# IoT_modules_atmega328_kinemata_v3.net
KiCad netlist of a schematic drawn in EAGLE
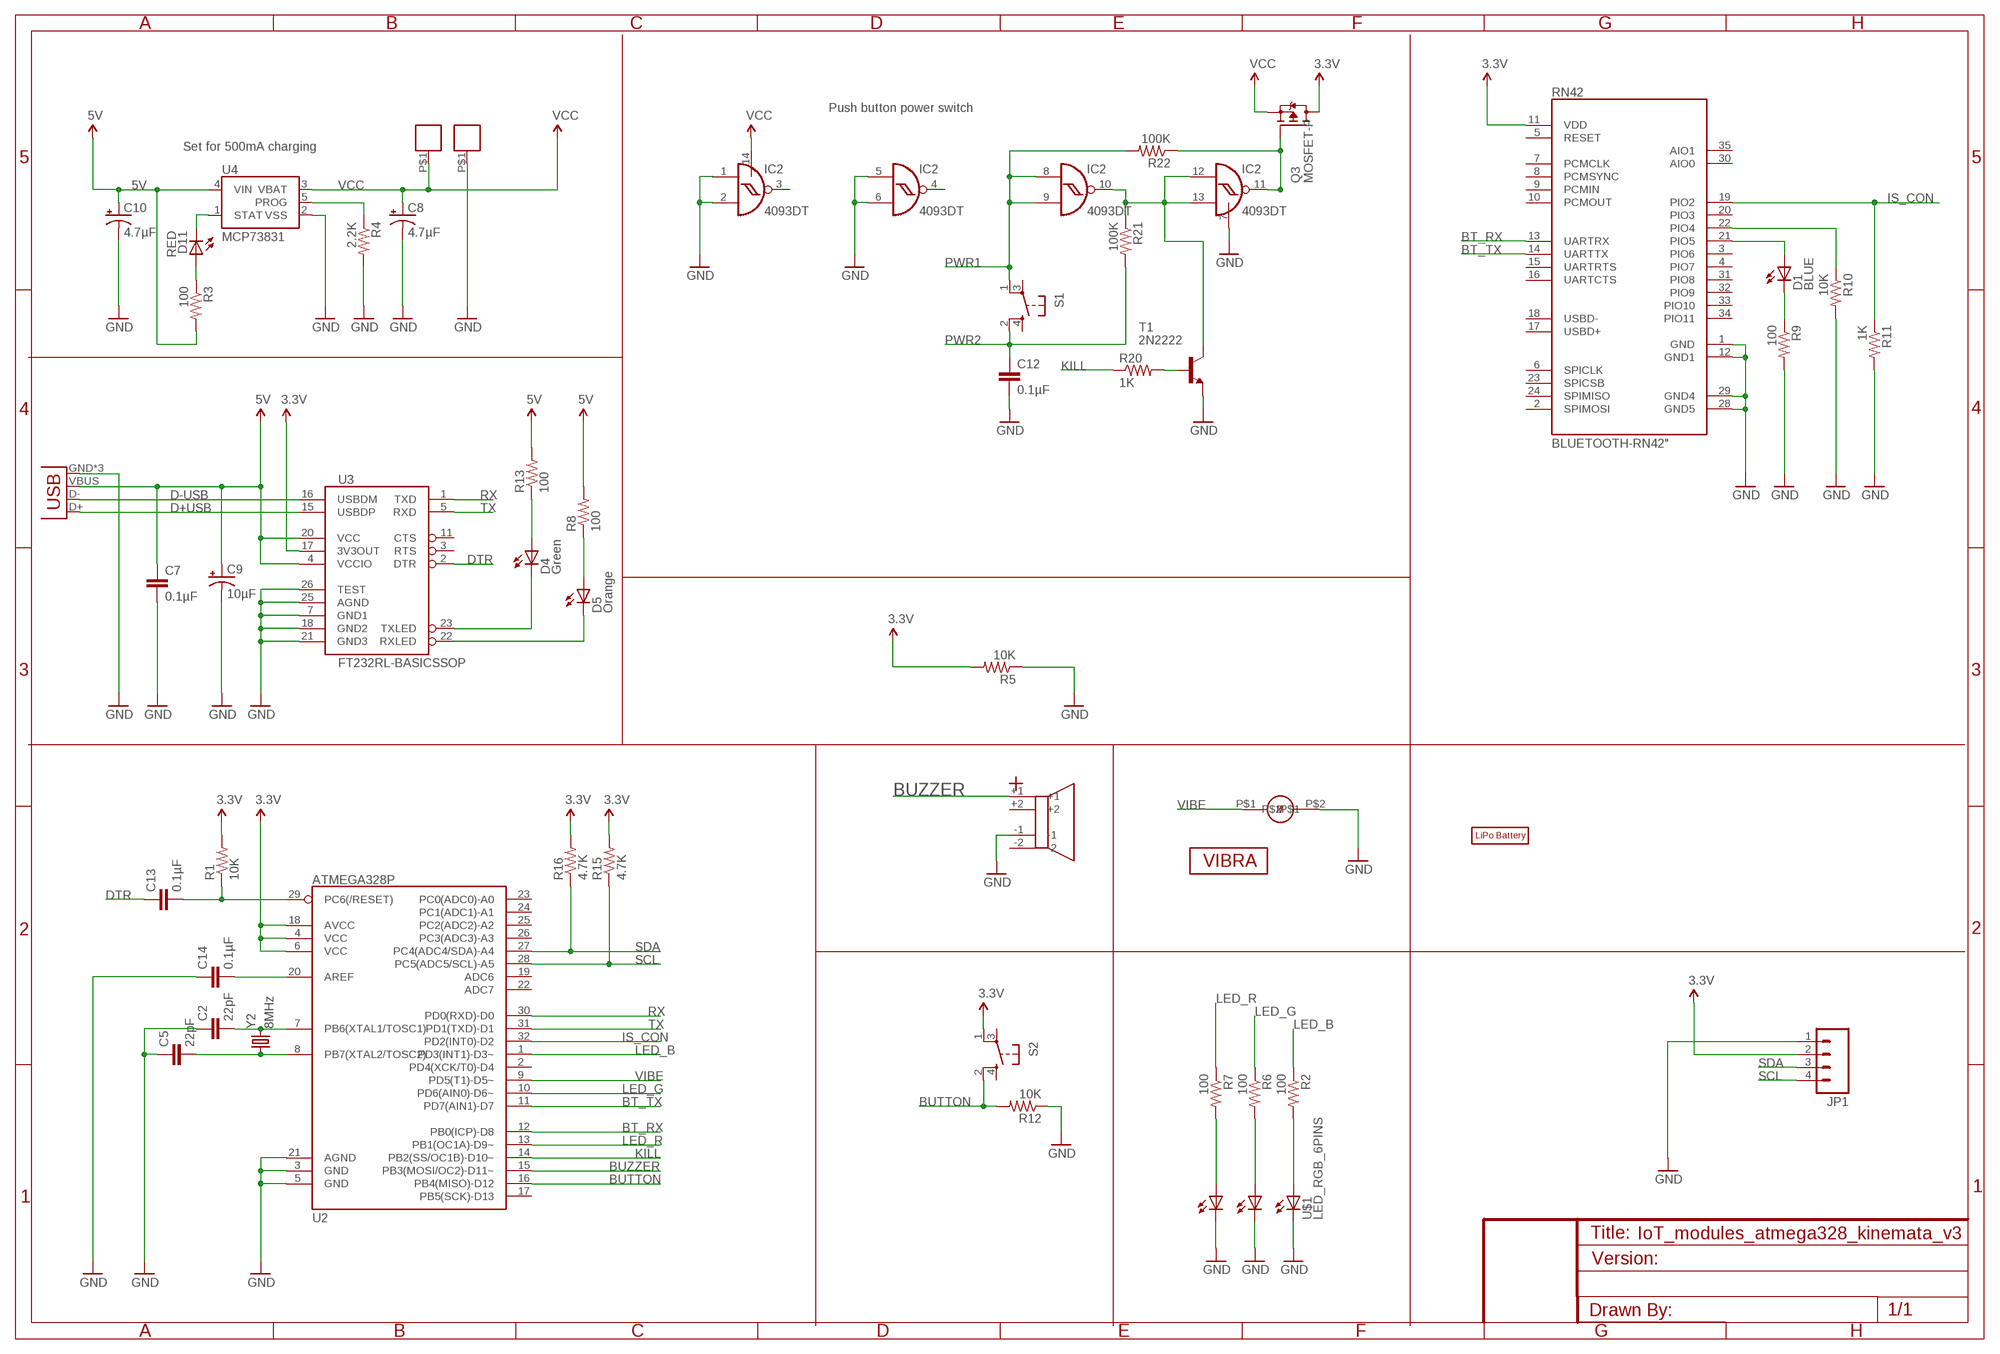
[diagram p0: schematic, sheet 1]

(export (version "E")
  (design (tool "Eeschema 10.0.6"))
  (components
    (comp (ref "BAT+2")
      (value "LIPO_PAD")
      (footprint "eagle-import:LIPO_PAD")
      (libsource (lib "eagle-import") (part "LIPO_PAD"))
    )
    (comp (ref "BAT-1")
      (value "LIPO_PAD")
      (footprint "eagle-import:LIPO_PAD")
      (libsource (lib "eagle-import") (part "LIPO_PAD"))
    )
    (comp (ref "C2")
      (value "22pF")
      (footprint "eagle-import:1206")
      (libsource (lib "eagle-import") (part "CAP1206"))
    )
    (comp (ref "C5")
      (value "22pF")
      (footprint "eagle-import:1206")
      (libsource (lib "eagle-import") (part "CAP1206"))
    )
    (comp (ref "C7")
      (value "0.1µF")
      (footprint "eagle-import:1206")
      (libsource (lib "eagle-import") (part "CAP1206"))
    )
    (comp (ref "C8")
      (value "4.7µF")
      (footprint "eagle-import:EIA3216")
      (libsource (lib "eagle-import") (part "CAP_POL1206"))
    )
    (comp (ref "C9")
      (value "10µF")
      (footprint "eagle-import:EIA3216")
      (libsource (lib "eagle-import") (part "CAP_POL1206"))
    )
    (comp (ref "C10")
      (value "4.7µF")
      (footprint "eagle-import:EIA3216")
      (libsource (lib "eagle-import") (part "CAP_POL1206"))
    )
    (comp (ref "C12")
      (value "0.1µF")
      (footprint "eagle-import:1206")
      (libsource (lib "eagle-import") (part "CAP1206"))
    )
    (comp (ref "C13")
      (value "0.1µF")
      (footprint "eagle-import:1206")
      (libsource (lib "eagle-import") (part "CAP1206"))
    )
    (comp (ref "C14")
      (value "0.1µF")
      (footprint "eagle-import:1206")
      (libsource (lib "eagle-import") (part "CAP1206"))
    )
    (comp (ref "D1")
      (value "BLUE")
      (footprint "eagle-import:LED-1206")
      (libsource (lib "eagle-import") (part "LED1206"))
    )
    (comp (ref "D4")
      (value "Green")
      (footprint "eagle-import:LED-1206")
      (libsource (lib "eagle-import") (part "LED1206"))
    )
    (comp (ref "D5")
      (value "Orange")
      (footprint "eagle-import:LED-1206")
      (libsource (lib "eagle-import") (part "LED1206"))
    )
    (comp (ref "D11")
      (value "RED")
      (footprint "eagle-import:LED-1206")
      (libsource (lib "eagle-import") (part "LED1206"))
    )
    (comp (ref "IC2")
      (value "4093DT")
      (footprint "eagle-import:MC14093B-TSSOP14")
      (libsource (lib "eagle-import") (part "4093DT"))
    )
    (comp (ref "JP1")
      (value "M04LONGPADS")
      (footprint "eagle-import:1X04_LONGPADS")
      (libsource (lib "eagle-import") (part "M04LONGPADS"))
    )
    (comp (ref "JP6")
      (value "USB-MICROB")
      (footprint "eagle-import:USB-MICROB")
      (libsource (lib "eagle-import") (part "USB-MICROB"))
    )
    (comp (ref "Q3")
      (value "MOSFET-P")
      (footprint "eagle-import:SOT23")
      (libsource (lib "eagle-import") (part "MOSFET-P"))
    )
    (comp (ref "R1")
      (value "10K")
      (footprint "eagle-import:1206")
      (libsource (lib "eagle-import") (part "RESISTOR1206"))
    )
    (comp (ref "R2")
      (value "100")
      (footprint "eagle-import:1206")
      (libsource (lib "eagle-import") (part "RESISTOR1206"))
    )
    (comp (ref "R3")
      (value "100")
      (footprint "eagle-import:1206")
      (libsource (lib "eagle-import") (part "RESISTOR1206"))
    )
    (comp (ref "R4")
      (value "2.2K")
      (footprint "eagle-import:1206")
      (libsource (lib "eagle-import") (part "RESISTOR1206"))
    )
    (comp (ref "R5")
      (value "10K")
      (footprint "eagle-import:1206")
      (libsource (lib "eagle-import") (part "RESISTOR1206"))
    )
    (comp (ref "R6")
      (value "100")
      (footprint "eagle-import:1206")
      (libsource (lib "eagle-import") (part "RESISTOR1206"))
    )
    (comp (ref "R7")
      (value "100")
      (footprint "eagle-import:1206")
      (libsource (lib "eagle-import") (part "RESISTOR1206"))
    )
    (comp (ref "R8")
      (value "100")
      (footprint "eagle-import:1206")
      (libsource (lib "eagle-import") (part "RESISTOR1206"))
    )
    (comp (ref "R9")
      (value "100")
      (footprint "eagle-import:1206")
      (libsource (lib "eagle-import") (part "RESISTOR1206"))
    )
    (comp (ref "R10")
      (value "10K")
      (footprint "eagle-import:1206")
      (libsource (lib "eagle-import") (part "RESISTOR1206"))
    )
    (comp (ref "R11")
      (value "1K")
      (footprint "eagle-import:1206")
      (libsource (lib "eagle-import") (part "RESISTOR1206"))
    )
    (comp (ref "R12")
      (value "10K")
      (footprint "eagle-import:1206")
      (libsource (lib "eagle-import") (part "RESISTOR1206"))
    )
    (comp (ref "R13")
      (value "100")
      (footprint "eagle-import:1206")
      (libsource (lib "eagle-import") (part "RESISTOR1206"))
    )
    (comp (ref "R15")
      (value "4.7K")
      (footprint "eagle-import:1206")
      (libsource (lib "eagle-import") (part "RESISTOR1206"))
    )
    (comp (ref "R16")
      (value "4.7K")
      (footprint "eagle-import:1206")
      (libsource (lib "eagle-import") (part "RESISTOR1206"))
    )
    (comp (ref "R20")
      (value "1K")
      (footprint "eagle-import:1206")
      (libsource (lib "eagle-import") (part "RESISTOR1206"))
    )
    (comp (ref "R21")
      (value "100K")
      (footprint "eagle-import:1206")
      (libsource (lib "eagle-import") (part "RESISTOR1206"))
    )
    (comp (ref "R22")
      (value "100K")
      (footprint "eagle-import:1206")
      (libsource (lib "eagle-import") (part "RESISTOR1206"))
    )
    (comp (ref "RN42")
      (value "BLUETOOTH-RN42\"")
      (footprint "eagle-import:RN42")
      (libsource (lib "eagle-import") (part "BLUETOOTH-RN42{dblquote}"))
    )
    (comp (ref "S1")
      (value "TAC_SWITCH_SIDEWAY")
      (footprint "eagle-import:TACTILE_SWITCH_ANGLE_SMD")
      (libsource (lib "eagle-import") (part "TAC_SWITCH_SIDEWAY"))
    )
    (comp (ref "S2")
      (value "TAC_SWITCH_SIDEWAY")
      (footprint "eagle-import:TACTILE_SWITCH_ANGLE_SMD")
      (libsource (lib "eagle-import") (part "TAC_SWITCH_SIDEWAY"))
    )
    (comp (ref "T1")
      (value "2N2222")
      (footprint "eagle-import:TO92-EBC-OVAL")
      (libsource (lib "eagle-import") (part "2N2222"))
    )
    (comp (ref "U$1")
      (value "LED_RGB_6PINS")
      (footprint "eagle-import:LED_RGB_6PINS")
      (libsource (lib "eagle-import") (part "LED_RGB_6PINS"))
    )
    (comp (ref "U$2")
      (value "LIPO_BATTERY110MAH")
      (footprint "eagle-import:LIPO_BATTERY_110MAH")
      (libsource (lib "eagle-import") (part "LIPO_BATTERY110MAH"))
    )
    (comp (ref "U$3")
      (value "BUZZER_4PINS")
      (footprint "eagle-import:FARNELL_BUZZER_MAGNETIC_SMD_3V_2215091")
      (libsource (lib "eagle-import") (part "BUZZER_4PINS"))
    )
    (comp (ref "U$4")
      (value "VIBRATION_MOTOR_SHAPE")
      (footprint "eagle-import:VIBRATION_MOTOR_SHAPE")
      (libsource (lib "eagle-import") (part "VIBRATION_MOTOR_SHAPE"))
    )
    (comp (ref "U$5")
      (value "VIBRATION_MOTOR")
      (footprint "eagle-import:VIBRATION_MOTOR_CABLE")
      (libsource (lib "eagle-import") (part "VIBRATION_MOTOR"))
    )
    (comp (ref "U2")
      (value "ATMEGA328P")
      (footprint "eagle-import:TQFP32-08")
      (libsource (lib "eagle-import") (part "ATMEGA328_SMT"))
    )
    (comp (ref "U3")
      (value "FT232RL-BASICSSOP")
      (footprint "eagle-import:SSOP28DB")
      (libsource (lib "eagle-import") (part "FT232RL-BASICSSOP"))
    )
    (comp (ref "U4")
      (value "MCP73831")
      (footprint "eagle-import:SOT23-5")
      (libsource (lib "eagle-import") (part "MCP73831"))
    )
    (comp (ref "Y2")
      (value "8MHz")
      (footprint "eagle-import:CRYSTAL_8MHZ_SMD_FARNELL_2101329")
      (libsource (lib "eagle-import") (part "CRYSTAL_2PINS5X3.2"))
    )
  )
  (nets
    (net (code "1") (name "/BT_RX") (class "Default")
      (node (ref "RN42") (pin "13") (pinfunction "UARTRX_13") (pintype "bidirectional"))
      (node (ref "U2") (pin "12") (pinfunction "PB0(ICP)-D8_12") (pintype "bidirectional"))
    )
    (net (code "2") (name "/BT_TX") (class "Default")
      (node (ref "RN42") (pin "14") (pinfunction "UARTTX_14") (pintype "bidirectional"))
      (node (ref "U2") (pin "11") (pinfunction "PD7(AIN1)-D7_11") (pintype "bidirectional"))
    )
    (net (code "3") (name "/BUTTON") (class "Default")
      (node (ref "R12") (pin "2") (pinfunction "2_2") (pintype "passive"))
      (node (ref "S2") (pin "2") (pinfunction "B2_2") (pintype "passive"))
      (node (ref "U2") (pin "16") (pinfunction "PB4(MISO)-D12_16") (pintype "bidirectional"))
    )
    (net (code "4") (name "/BUZZER") (class "Default")
      (node (ref "U$3") (pin "+1") (pinfunction "+1_+1") (pintype "bidirectional"))
      (node (ref "U2") (pin "15") (pinfunction "PB3(MOSI/OC2)-D11~{}_15") (pintype "bidirectional"))
    )
    (net (code "5") (name "/D+USB") (class "Default")
      (node (ref "JP6") (pin "D+") (pinfunction "D+_D+") (pintype "bidirectional"))
      (node (ref "U3") (pin "15") (pinfunction "USBDP_15") (pintype "bidirectional"))
    )
    (net (code "6") (name "/D-USB") (class "Default")
      (node (ref "JP6") (pin "D-") (pinfunction "D-_D-") (pintype "bidirectional"))
      (node (ref "U3") (pin "16") (pinfunction "USBDM_16") (pintype "bidirectional"))
    )
    (net (code "7") (name "/DTR") (class "Default")
      (node (ref "C13") (pin "1") (pinfunction "1_1") (pintype "passive"))
      (node (ref "U3") (pin "2") (pinfunction "DTR_2") (pintype "bidirectional"))
    )
    (net (code "8") (name "/IS_CON") (class "Default")
      (node (ref "R11") (pin "1") (pinfunction "1_1") (pintype "passive"))
      (node (ref "RN42") (pin "19") (pinfunction "PIO2_19") (pintype "bidirectional"))
      (node (ref "U2") (pin "32") (pinfunction "PD2(INT0)-D2_32") (pintype "bidirectional"))
    )
    (net (code "9") (name "/KILL") (class "Default")
      (node (ref "R20") (pin "1") (pinfunction "1_1") (pintype "passive"))
      (node (ref "U2") (pin "14") (pinfunction "PB2(SS/OC1B)-D10~{}_14") (pintype "bidirectional"))
    )
    (net (code "10") (name "/LED_B") (class "Default")
      (node (ref "R2") (pin "1") (pinfunction "1_1") (pintype "passive"))
      (node (ref "U2") (pin "1") (pinfunction "PD3(INT1)-D3~{}_1") (pintype "bidirectional"))
    )
    (net (code "11") (name "/LED_G") (class "Default")
      (node (ref "R6") (pin "1") (pinfunction "1_1") (pintype "passive"))
      (node (ref "U2") (pin "10") (pinfunction "PD6(AIN0)-D6~{}_10") (pintype "bidirectional"))
    )
    (net (code "12") (name "/LED_R") (class "Default")
      (node (ref "R7") (pin "1") (pinfunction "1_1") (pintype "passive"))
      (node (ref "U2") (pin "13") (pinfunction "PB1(OC1A)-D9~{}_13") (pintype "bidirectional"))
    )
    (net (code "13") (name "/PWR1") (class "Default")
      (node (ref "IC2") (pin "8") (pinfunction "8_8") (pintype "input"))
      (node (ref "IC2") (pin "9") (pinfunction "9_9") (pintype "input"))
      (node (ref "R22") (pin "2") (pinfunction "2_2") (pintype "passive"))
      (node (ref "S1") (pin "1") (pinfunction "A2_1") (pintype "passive"))
    )
    (net (code "14") (name "/PWR2") (class "Default")
      (node (ref "C12") (pin "1") (pinfunction "1_1") (pintype "passive"))
      (node (ref "R21") (pin "2") (pinfunction "2_2") (pintype "passive"))
      (node (ref "S1") (pin "2") (pinfunction "B2_2") (pintype "passive"))
    )
    (net (code "15") (name "/RX") (class "Default")
      (node (ref "U2") (pin "30") (pinfunction "PD0(RXD)-D0_30") (pintype "bidirectional"))
      (node (ref "U3") (pin "1") (pinfunction "TXD_1") (pintype "output"))
    )
    (net (code "16") (name "/SCL") (class "Default")
      (node (ref "JP1") (pin "4") (pinfunction "4_4") (pintype "passive"))
      (node (ref "R15") (pin "1") (pinfunction "1_1") (pintype "passive"))
      (node (ref "U2") (pin "28") (pinfunction "PC5(ADC5/SCL)-A5_28") (pintype "bidirectional"))
    )
    (net (code "17") (name "/SDA") (class "Default")
      (node (ref "JP1") (pin "3") (pinfunction "3_3") (pintype "passive"))
      (node (ref "R16") (pin "1") (pinfunction "1_1") (pintype "passive"))
      (node (ref "U2") (pin "27") (pinfunction "PC4(ADC4/SDA)-A4_27") (pintype "bidirectional"))
    )
    (net (code "18") (name "/TX") (class "Default")
      (node (ref "U2") (pin "31") (pinfunction "PD1(TXD)-D1_31") (pintype "bidirectional"))
      (node (ref "U3") (pin "5") (pinfunction "RXD_5") (pintype "input"))
    )
    (net (code "19") (name "/VIBE") (class "Default")
      (node (ref "U$5") (pin "P$1") (pinfunction "P$1_P$1") (pintype "bidirectional"))
      (node (ref "U2") (pin "9") (pinfunction "PD5(T1)-D5~{}_9") (pintype "bidirectional"))
    )
    (net (code "20") (name "3.3V") (class "Default")
      (node (ref "JP1") (pin "2") (pinfunction "2_2") (pintype "passive"))
      (node (ref "Q3") (pin "3") (pinfunction "D_3") (pintype "passive"))
      (node (ref "R1") (pin "2") (pinfunction "2_2") (pintype "passive"))
      (node (ref "R15") (pin "2") (pinfunction "2_2") (pintype "passive"))
      (node (ref "R16") (pin "2") (pinfunction "2_2") (pintype "passive"))
      (node (ref "R5") (pin "2") (pinfunction "2_2") (pintype "passive"))
      (node (ref "RN42") (pin "11") (pinfunction "VDD_11") (pintype "bidirectional"))
      (node (ref "S2") (pin "1") (pinfunction "A2_1") (pintype "passive"))
      (node (ref "U2") (pin "18") (pinfunction "AVCC_18") (pintype "bidirectional"))
      (node (ref "U2") (pin "4") (pinfunction "VCC_4") (pintype "bidirectional"))
      (node (ref "U2") (pin "6") (pinfunction "VCC_6") (pintype "bidirectional"))
      (node (ref "U3") (pin "17") (pinfunction "3V3OUT_17") (pintype "output"))
    )
    (net (code "21") (name "5V") (class "Default")
      (node (ref "C10") (pin "A") (pinfunction "+_A") (pintype "passive"))
      (node (ref "C7") (pin "1") (pinfunction "1_1") (pintype "passive"))
      (node (ref "C9") (pin "A") (pinfunction "+_A") (pintype "passive"))
      (node (ref "JP6") (pin "VBUS") (pinfunction "VBUS_VBUS") (pintype "bidirectional"))
      (node (ref "R13") (pin "2") (pinfunction "2_2") (pintype "passive"))
      (node (ref "R3") (pin "2") (pinfunction "2_2") (pintype "passive"))
      (node (ref "R8") (pin "2") (pinfunction "2_2") (pintype "passive"))
      (node (ref "U3") (pin "20") (pinfunction "VCC_20") (pintype "power_in"))
      (node (ref "U3") (pin "4") (pinfunction "VCCIO_4") (pintype "power_in"))
      (node (ref "U4") (pin "4") (pinfunction "VIN_4") (pintype "power_in"))
    )
    (net (code "22") (name "GND") (class "Default")
      (node (ref "BAT-1") (pin "P$1") (pinfunction "P$1_P$1") (pintype "power_in"))
      (node (ref "C10") (pin "C") (pinfunction "-_C") (pintype "passive"))
      (node (ref "C12") (pin "2") (pinfunction "2_2") (pintype "passive"))
      (node (ref "C14") (pin "1") (pinfunction "1_1") (pintype "passive"))
      (node (ref "C2") (pin "1") (pinfunction "1_1") (pintype "passive"))
      (node (ref "C5") (pin "1") (pinfunction "1_1") (pintype "passive"))
      (node (ref "C7") (pin "2") (pinfunction "2_2") (pintype "passive"))
      (node (ref "C8") (pin "C") (pinfunction "-_C") (pintype "passive"))
      (node (ref "C9") (pin "C") (pinfunction "-_C") (pintype "passive"))
      (node (ref "IC2") (pin "1") (pinfunction "1_1") (pintype "input"))
      (node (ref "IC2") (pin "2") (pinfunction "2_2") (pintype "input"))
      (node (ref "IC2") (pin "5") (pinfunction "5_5") (pintype "input"))
      (node (ref "IC2") (pin "6") (pinfunction "6_6") (pintype "input"))
      (node (ref "IC2") (pin "7") (pinfunction "7_7") (pintype "power_in"))
      (node (ref "JP1") (pin "1") (pinfunction "1_1") (pintype "passive"))
      (node (ref "JP6") (pin "GND") (pinfunction "GND_GND") (pintype "bidirectional"))
      (node (ref "JP6") (pin "MT1") (pinfunction "GND_MT1") (pintype "bidirectional"))
      (node (ref "JP6") (pin "MT2") (pinfunction "GND_MT2") (pintype "bidirectional"))
      (node (ref "R10") (pin "2") (pinfunction "2_2") (pintype "passive"))
      (node (ref "R11") (pin "2") (pinfunction "2_2") (pintype "passive"))
      (node (ref "R12") (pin "1") (pinfunction "1_1") (pintype "passive"))
      (node (ref "R4") (pin "2") (pinfunction "2_2") (pintype "passive"))
      (node (ref "R5") (pin "1") (pinfunction "1_1") (pintype "passive"))
      (node (ref "R9") (pin "2") (pinfunction "2_2") (pintype "passive"))
      (node (ref "RN42") (pin "1") (pinfunction "GND_1") (pintype "bidirectional"))
      (node (ref "RN42") (pin "12") (pinfunction "GND1_12") (pintype "bidirectional"))
      (node (ref "RN42") (pin "28") (pinfunction "GND5_28") (pintype "bidirectional"))
      (node (ref "RN42") (pin "29") (pinfunction "GND4_29") (pintype "bidirectional"))
      (node (ref "T1") (pin "E") (pinfunction "E_E") (pintype "passive"))
      (node (ref "U$1") (pin "BC") (pinfunction "BC_BC") (pintype "passive"))
      (node (ref "U$1") (pin "GC") (pinfunction "GC_GC") (pintype "passive"))
      (node (ref "U$1") (pin "RC") (pinfunction "RC_RC") (pintype "passive"))
      (node (ref "U$3") (pin "-1") (pinfunction "-1_-1") (pintype "bidirectional"))
      (node (ref "U$5") (pin "P$2") (pinfunction "P$2_P$2") (pintype "bidirectional"))
      (node (ref "U2") (pin "21") (pinfunction "AGND_21") (pintype "bidirectional"))
      (node (ref "U2") (pin "3") (pinfunction "GND_3") (pintype "bidirectional"))
      (node (ref "U2") (pin "5") (pinfunction "GND_5") (pintype "bidirectional"))
      (node (ref "U3") (pin "18") (pinfunction "GND2_18") (pintype "power_in"))
      (node (ref "U3") (pin "21") (pinfunction "GND3_21") (pintype "power_in"))
      (node (ref "U3") (pin "25") (pinfunction "AGND_25") (pintype "power_in"))
      (node (ref "U3") (pin "26") (pinfunction "TEST_26") (pintype "input"))
      (node (ref "U3") (pin "7") (pinfunction "GND1_7") (pintype "power_in"))
      (node (ref "U4") (pin "2") (pinfunction "VSS_2") (pintype "power_in"))
    )
    (net (code "23") (name "Net-(D1-PadC)") (class "Default")
      (node (ref "D1") (pin "C") (pinfunction "C_C") (pintype "passive"))
      (node (ref "R9") (pin "1") (pinfunction "1_1") (pintype "passive"))
    )
    (net (code "24") (name "Net-(D4-PadA)") (class "Default")
      (node (ref "D4") (pin "A") (pinfunction "A_A") (pintype "passive"))
      (node (ref "R13") (pin "1") (pinfunction "1_1") (pintype "passive"))
    )
    (net (code "25") (name "Net-(D5-PadA)") (class "Default")
      (node (ref "D5") (pin "A") (pinfunction "A_A") (pintype "passive"))
      (node (ref "R8") (pin "1") (pinfunction "1_1") (pintype "passive"))
    )
    (net (code "26") (name "Net-(D11-PadA)") (class "Default")
      (node (ref "D11") (pin "A") (pinfunction "A_A") (pintype "passive"))
      (node (ref "R3") (pin "1") (pinfunction "1_1") (pintype "passive"))
    )
    (net (code "27") (name "Net-(IC2-Pad10)") (class "Default")
      (node (ref "IC2") (pin "10") (pinfunction "10_10") (pintype "output"))
      (node (ref "IC2") (pin "12") (pinfunction "12_12") (pintype "input"))
      (node (ref "IC2") (pin "13") (pinfunction "13_13") (pintype "input"))
      (node (ref "R21") (pin "1") (pinfunction "1_1") (pintype "passive"))
      (node (ref "T1") (pin "C") (pinfunction "C_C") (pintype "passive"))
    )
    (net (code "28") (name "Net-(Q3-G)") (class "Default")
      (node (ref "IC2") (pin "11") (pinfunction "11_11") (pintype "output"))
      (node (ref "Q3") (pin "1") (pinfunction "G_1") (pintype "passive"))
      (node (ref "R22") (pin "1") (pinfunction "1_1") (pintype "passive"))
    )
    (net (code "29") (name "Net-(R2-Pad2)") (class "Default")
      (node (ref "R2") (pin "2") (pinfunction "2_2") (pintype "passive"))
      (node (ref "U$1") (pin "GA") (pinfunction "GA_GA") (pintype "passive"))
    )
    (net (code "30") (name "Net-(R6-Pad2)") (class "Default")
      (node (ref "R6") (pin "2") (pinfunction "2_2") (pintype "passive"))
      (node (ref "U$1") (pin "RA") (pinfunction "RA_RA") (pintype "passive"))
    )
    (net (code "31") (name "Net-(R7-Pad2)") (class "Default")
      (node (ref "R7") (pin "2") (pinfunction "2_2") (pintype "passive"))
      (node (ref "U$1") (pin "BA") (pinfunction "BA_BA") (pintype "passive"))
    )
    (net (code "32") (name "Net-(R20-Pad2)") (class "Default")
      (node (ref "R20") (pin "2") (pinfunction "2_2") (pintype "passive"))
      (node (ref "T1") (pin "B") (pinfunction "B_B") (pintype "passive"))
    )
    (net (code "33") (name "Net-(RN42-PIO4)") (class "Default")
      (node (ref "R10") (pin "1") (pinfunction "1_1") (pintype "passive"))
      (node (ref "RN42") (pin "22") (pinfunction "PIO4_22") (pintype "bidirectional"))
    )
    (net (code "34") (name "Net-(RN42-PIO5)") (class "Default")
      (node (ref "D1") (pin "A") (pinfunction "A_A") (pintype "passive"))
      (node (ref "RN42") (pin "21") (pinfunction "PIO5_21") (pintype "bidirectional"))
    )
    (net (code "35") (name "Net-(U2-AREF)") (class "Default")
      (node (ref "C14") (pin "2") (pinfunction "2_2") (pintype "passive"))
      (node (ref "U2") (pin "20") (pinfunction "AREF_20") (pintype "bidirectional"))
    )
    (net (code "36") (name "Net-(U2-PB6(XTAL1{slash}TOSC1))") (class "Default")
      (node (ref "C2") (pin "2") (pinfunction "2_2") (pintype "passive"))
      (node (ref "U2") (pin "7") (pinfunction "PB6(XTAL1/TOSC1)_7") (pintype "bidirectional"))
      (node (ref "Y2") (pin "P$2") (pinfunction "2_P$2") (pintype "passive"))
    )
    (net (code "37") (name "Net-(U2-PB7(XTAL2{slash}TOSC2))") (class "Default")
      (node (ref "C5") (pin "2") (pinfunction "2_2") (pintype "passive"))
      (node (ref "U2") (pin "8") (pinfunction "PB7(XTAL2/TOSC2)_8") (pintype "bidirectional"))
      (node (ref "Y2") (pin "P$1") (pinfunction "1_P$1") (pintype "passive"))
    )
    (net (code "38") (name "Net-(U2-PC6({slash}RESET))") (class "Default")
      (node (ref "C13") (pin "2") (pinfunction "2_2") (pintype "passive"))
      (node (ref "R1") (pin "1") (pinfunction "1_1") (pintype "passive"))
      (node (ref "U2") (pin "29") (pinfunction "PC6(/RESET)_29") (pintype "bidirectional"))
    )
    (net (code "39") (name "Net-(U3-RXLED)") (class "Default")
      (node (ref "D5") (pin "C") (pinfunction "C_C") (pintype "passive"))
      (node (ref "U3") (pin "22") (pinfunction "RXLED_22") (pintype "bidirectional"))
    )
    (net (code "40") (name "Net-(U3-TXLED)") (class "Default")
      (node (ref "D4") (pin "C") (pinfunction "C_C") (pintype "passive"))
      (node (ref "U3") (pin "23") (pinfunction "TXLED_23") (pintype "bidirectional"))
    )
    (net (code "41") (name "Net-(U4-PROG)") (class "Default")
      (node (ref "R4") (pin "1") (pinfunction "1_1") (pintype "passive"))
      (node (ref "U4") (pin "5") (pinfunction "PROG_5") (pintype "input"))
    )
    (net (code "42") (name "Net-(U4-STAT)") (class "Default")
      (node (ref "D11") (pin "C") (pinfunction "C_C") (pintype "passive"))
      (node (ref "U4") (pin "1") (pinfunction "STAT_1") (pintype "output"))
    )
    (net (code "43") (name "VCC") (class "Default")
      (node (ref "BAT+2") (pin "P$1") (pinfunction "P$1_P$1") (pintype "power_in"))
      (node (ref "C8") (pin "A") (pinfunction "+_A") (pintype "passive"))
      (node (ref "IC2") (pin "14") (pinfunction "14_14") (pintype "power_in"))
      (node (ref "Q3") (pin "2") (pinfunction "S_2") (pintype "passive"))
      (node (ref "U4") (pin "3") (pinfunction "VBAT_3") (pintype "power_in"))
    )
    (net (code "44") (name "unconnected-(IC2-Pad3)") (class "Default")
      (node (ref "IC2") (pin "3") (pinfunction "3_3") (pintype "output"))
    )
    (net (code "45") (name "unconnected-(IC2-Pad4)") (class "Default")
      (node (ref "IC2") (pin "4") (pinfunction "4_4") (pintype "output"))
    )
    (net (code "46") (name "unconnected-(RN42-AIO0-Pad30)") (class "Default")
      (node (ref "RN42") (pin "30") (pinfunction "AIO0_30") (pintype "bidirectional"))
    )
    (net (code "47") (name "unconnected-(RN42-AIO1-Pad35)") (class "Default")
      (node (ref "RN42") (pin "35") (pinfunction "AIO1_35") (pintype "bidirectional"))
    )
    (net (code "48") (name "unconnected-(RN42-PCMCLK-Pad7)") (class "Default")
      (node (ref "RN42") (pin "7") (pinfunction "PCMCLK_7") (pintype "bidirectional"))
    )
    (net (code "49") (name "unconnected-(RN42-PCMIN-Pad9)") (class "Default")
      (node (ref "RN42") (pin "9") (pinfunction "PCMIN_9") (pintype "bidirectional"))
    )
    (net (code "50") (name "unconnected-(RN42-PCMOUT-Pad10)") (class "Default")
      (node (ref "RN42") (pin "10") (pinfunction "PCMOUT_10") (pintype "bidirectional"))
    )
    (net (code "51") (name "unconnected-(RN42-PCMSYNC-Pad8)") (class "Default")
      (node (ref "RN42") (pin "8") (pinfunction "PCMSYNC_8") (pintype "bidirectional"))
    )
    (net (code "52") (name "unconnected-(RN42-PIO3-Pad20)") (class "Default")
      (node (ref "RN42") (pin "20") (pinfunction "PIO3_20") (pintype "bidirectional"))
    )
    (net (code "53") (name "unconnected-(RN42-PIO6-Pad3)") (class "Default")
      (node (ref "RN42") (pin "3") (pinfunction "PIO6_3") (pintype "bidirectional"))
    )
    (net (code "54") (name "unconnected-(RN42-PIO7-Pad4)") (class "Default")
      (node (ref "RN42") (pin "4") (pinfunction "PIO7_4") (pintype "bidirectional"))
    )
    (net (code "55") (name "unconnected-(RN42-PIO8-Pad31)") (class "Default")
      (node (ref "RN42") (pin "31") (pinfunction "PIO8_31") (pintype "bidirectional"))
    )
    (net (code "56") (name "unconnected-(RN42-PIO9-Pad32)") (class "Default")
      (node (ref "RN42") (pin "32") (pinfunction "PIO9_32") (pintype "bidirectional"))
    )
    (net (code "57") (name "unconnected-(RN42-PIO10-Pad33)") (class "Default")
      (node (ref "RN42") (pin "33") (pinfunction "PIO10_33") (pintype "bidirectional"))
    )
    (net (code "58") (name "unconnected-(RN42-PIO11-Pad34)") (class "Default")
      (node (ref "RN42") (pin "34") (pinfunction "PIO11_34") (pintype "bidirectional"))
    )
    (net (code "59") (name "unconnected-(RN42-RESET-Pad5)") (class "Default")
      (node (ref "RN42") (pin "5") (pinfunction "RESET_5") (pintype "bidirectional"))
    )
    (net (code "60") (name "unconnected-(RN42-SPICLK-Pad6)") (class "Default")
      (node (ref "RN42") (pin "6") (pinfunction "SPICLK_6") (pintype "bidirectional"))
    )
    (net (code "61") (name "unconnected-(RN42-SPICSB-Pad23)") (class "Default")
      (node (ref "RN42") (pin "23") (pinfunction "SPICSB_23") (pintype "bidirectional"))
    )
    (net (code "62") (name "unconnected-(RN42-SPIMISO-Pad24)") (class "Default")
      (node (ref "RN42") (pin "24") (pinfunction "SPIMISO_24") (pintype "bidirectional"))
    )
    (net (code "63") (name "unconnected-(RN42-SPIMOSI-Pad2)") (class "Default")
      (node (ref "RN42") (pin "2") (pinfunction "SPIMOSI_2") (pintype "bidirectional"))
    )
    (net (code "64") (name "unconnected-(RN42-UARTCTS-Pad16)") (class "Default")
      (node (ref "RN42") (pin "16") (pinfunction "UARTCTS_16") (pintype "bidirectional"))
    )
    (net (code "65") (name "unconnected-(RN42-UARTRTS-Pad15)") (class "Default")
      (node (ref "RN42") (pin "15") (pinfunction "UARTRTS_15") (pintype "bidirectional"))
    )
    (net (code "66") (name "unconnected-(RN42-USBD+-Pad17)") (class "Default")
      (node (ref "RN42") (pin "17") (pinfunction "USBD+_17") (pintype "bidirectional"))
    )
    (net (code "67") (name "unconnected-(RN42-USBD--Pad18)") (class "Default")
      (node (ref "RN42") (pin "18") (pinfunction "USBD-_18") (pintype "bidirectional"))
    )
    (net (code "68") (name "unconnected-(S1-A1-Pad3)") (class "Default")
      (node (ref "S1") (pin "3") (pinfunction "A1_3") (pintype "passive"))
    )
    (net (code "69") (name "unconnected-(S1-B1-Pad4)") (class "Default")
      (node (ref "S1") (pin "4") (pinfunction "B1_4") (pintype "passive"))
    )
    (net (code "70") (name "unconnected-(S2-A1-Pad3)") (class "Default")
      (node (ref "S2") (pin "3") (pinfunction "A1_3") (pintype "passive"))
    )
    (net (code "71") (name "unconnected-(S2-B1-Pad4)") (class "Default")
      (node (ref "S2") (pin "4") (pinfunction "B1_4") (pintype "passive"))
    )
    (net (code "72") (name "unconnected-(U$3-Pad+2)") (class "Default")
      (node (ref "U$3") (pin "+2") (pinfunction "+2_+2") (pintype "bidirectional"))
    )
    (net (code "73") (name "unconnected-(U$3-Pad-2)") (class "Default")
      (node (ref "U$3") (pin "-2") (pinfunction "-2_-2") (pintype "bidirectional"))
    )
    (net (code "74") (name "unconnected-(U2-ADC6-Pad19)") (class "Default")
      (node (ref "U2") (pin "19") (pinfunction "ADC6_19") (pintype "bidirectional"))
    )
    (net (code "75") (name "unconnected-(U2-ADC7-Pad22)") (class "Default")
      (node (ref "U2") (pin "22") (pinfunction "ADC7_22") (pintype "bidirectional"))
    )
    (net (code "76") (name "unconnected-(U2-PB5(SCK)-D13-Pad17)") (class "Default")
      (node (ref "U2") (pin "17") (pinfunction "PB5(SCK)-D13_17") (pintype "bidirectional"))
    )
    (net (code "77") (name "unconnected-(U2-PC0(ADC0)-A0-Pad23)") (class "Default")
      (node (ref "U2") (pin "23") (pinfunction "PC0(ADC0)-A0_23") (pintype "bidirectional"))
    )
    (net (code "78") (name "unconnected-(U2-PC1(ADC1)-A1-Pad24)") (class "Default")
      (node (ref "U2") (pin "24") (pinfunction "PC1(ADC1)-A1_24") (pintype "bidirectional"))
    )
    (net (code "79") (name "unconnected-(U2-PC2(ADC2)-A2-Pad25)") (class "Default")
      (node (ref "U2") (pin "25") (pinfunction "PC2(ADC2)-A2_25") (pintype "bidirectional"))
    )
    (net (code "80") (name "unconnected-(U2-PC3(ADC3)-A3-Pad26)") (class "Default")
      (node (ref "U2") (pin "26") (pinfunction "PC3(ADC3)-A3_26") (pintype "bidirectional"))
    )
    (net (code "81") (name "unconnected-(U2-PD4(XCK{slash}T0)-D4-Pad2)") (class "Default")
      (node (ref "U2") (pin "2") (pinfunction "PD4(XCK/T0)-D4_2") (pintype "bidirectional"))
    )
    (net (code "82") (name "unconnected-(U3-CTS-Pad11)") (class "Default")
      (node (ref "U3") (pin "11") (pinfunction "CTS_11") (pintype "bidirectional"))
    )
    (net (code "83") (name "unconnected-(U3-RTS-Pad3)") (class "Default")
      (node (ref "U3") (pin "3") (pinfunction "RTS_3") (pintype "bidirectional"))
    )
  )
)
